# aaasaver_v11.net
KiCad netlist of a schematic drawn in EAGLE
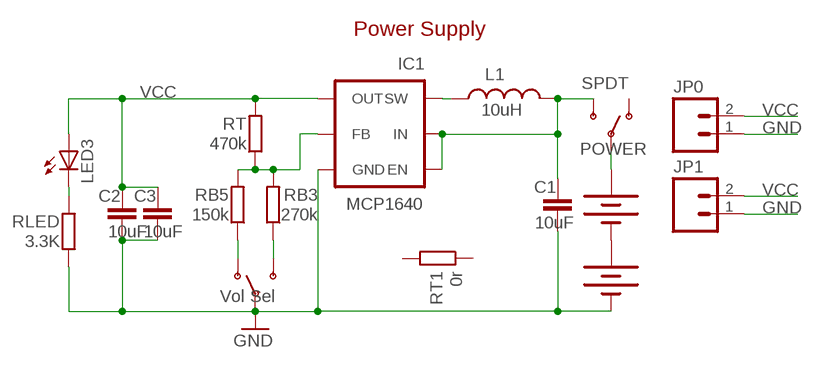
[diagram p0: schematic, sheet 1]

(export (version "E")
  (design (tool "Eeschema 10.0.6"))
  (components
    (comp (ref "AA1")
      (value "BATTERYAAA")
      (footprint "eagle-import:BATTERY-AAA")
      (libsource (lib "eagle-import") (part "BATTERYAAA"))
    )
    (comp (ref "AA2")
      (value "BATTERYAAA")
      (footprint "eagle-import:BATTERY-AAA")
      (libsource (lib "eagle-import") (part "BATTERYAAA"))
    )
    (comp (ref "C1")
      (value "10uF")
      (footprint "eagle-import:C0805")
      (libsource (lib "eagle-import") (part "C-EUC0805"))
    )
    (comp (ref "C2")
      (value "10uF")
      (footprint "eagle-import:C0805")
      (libsource (lib "eagle-import") (part "C-EUC0805"))
    )
    (comp (ref "C3")
      (value "10uF")
      (footprint "eagle-import:C0805")
      (libsource (lib "eagle-import") (part "C-EUC0805"))
    )
    (comp (ref "IC1")
      (value "MCP1640")
      (footprint "eagle-import:TSOT23-6")
      (libsource (lib "eagle-import") (part "MCP1640"))
    )
    (comp (ref "JP0")
      (value "M021X02_NO_SILK")
      (footprint "eagle-import:1X02_NO_SILK")
      (libsource (lib "eagle-import") (part "M021X02_NO_SILK"))
    )
    (comp (ref "JP1")
      (value "M021X02_NO_SILK")
      (footprint "eagle-import:1X02_NO_SILK")
      (libsource (lib "eagle-import") (part "M021X02_NO_SILK"))
    )
    (comp (ref "L1")
      (value "10uH")
      (footprint "eagle-import:INDUCTOR_D45")
      (libsource (lib "eagle-import") (part "INDUCTOR_SMDD45"))
    )
    (comp (ref "LED3")
      (value "0805")
      (footprint "eagle-import:CHIPLED_1206")
      (libsource (lib "eagle-import") (part "LEDCHIPLED_1206"))
    )
    (comp (ref "POWER")
      (value "SPDT")
      (footprint "eagle-import:SWITCH-SPDT-SMD")
      (libsource (lib "eagle-import") (part "SWITCH-SPSTSMD2"))
    )
    (comp (ref "RB3")
      (value "270k")
      (footprint "eagle-import:R0805")
      (libsource (lib "eagle-import") (part "R-EU_R0805"))
    )
    (comp (ref "RB5")
      (value "150k")
      (footprint "eagle-import:R0805")
      (libsource (lib "eagle-import") (part "R-EU_R0805"))
    )
    (comp (ref "RLED")
      (value "3.3K")
      (footprint "eagle-import:R0805")
      (libsource (lib "eagle-import") (part "R-EU_R0805"))
    )
    (comp (ref "RT")
      (value "470k")
      (footprint "eagle-import:R0805")
      (libsource (lib "eagle-import") (part "R-EU_R0805"))
    )
    (comp (ref "RT1")
      (value "0r")
      (footprint "eagle-import:R1206")
      (libsource (lib "eagle-import") (part "R-EU_R1206"))
    )
    (comp (ref "VOL1")
      (value "Vol Sel")
      (footprint "eagle-import:SWITCH-SPDT-SMD")
      (libsource (lib "eagle-import") (part "SWITCH-SPSTSMD2"))
    )
  )
  (nets
    (net (code "1") (name "/VCC") (class "Default")
      (node (ref "C2") (pin "1") (pinfunction "1_1") (pintype "passive"))
      (node (ref "C3") (pin "1") (pinfunction "1_1") (pintype "passive"))
      (node (ref "IC1") (pin "5") (pinfunction "OUT_5") (pintype "passive"))
      (node (ref "JP0") (pin "2") (pinfunction "2_2") (pintype "passive"))
      (node (ref "JP1") (pin "2") (pinfunction "2_2") (pintype "passive"))
      (node (ref "LED3") (pin "A") (pinfunction "A_A") (pintype "passive"))
      (node (ref "RT") (pin "2") (pinfunction "2_2") (pintype "passive"))
    )
    (net (code "2") (name "GND") (class "Default")
      (node (ref "AA2") (pin "GND@1") (pinfunction "-_GND@1") (pintype "power_in"))
      (node (ref "C1") (pin "2") (pinfunction "2_2") (pintype "passive"))
      (node (ref "C2") (pin "2") (pinfunction "2_2") (pintype "passive"))
      (node (ref "C3") (pin "2") (pinfunction "2_2") (pintype "passive"))
      (node (ref "IC1") (pin "2") (pinfunction "GND_2") (pintype "input"))
      (node (ref "JP0") (pin "1") (pinfunction "1_1") (pintype "passive"))
      (node (ref "JP1") (pin "1") (pinfunction "1_1") (pintype "passive"))
      (node (ref "RLED") (pin "1") (pinfunction "1_1") (pintype "passive"))
      (node (ref "VOL1") (pin "2") (pinfunction "P_2") (pintype "passive"))
    )
    (net (code "3") (name "Net-(AA1-+)") (class "Default")
      (node (ref "AA1") (pin "PWR@1") (pinfunction "+_PWR@1") (pintype "power_in"))
      (node (ref "POWER") (pin "2") (pinfunction "P_2") (pintype "passive"))
    )
    (net (code "4") (name "Net-(AA1--)") (class "Default")
      (node (ref "AA1") (pin "GND@1") (pinfunction "-_GND@1") (pintype "power_in"))
      (node (ref "AA2") (pin "PWR@1") (pinfunction "+_PWR@1") (pintype "power_in"))
    )
    (net (code "5") (name "Net-(IC1-EN)") (class "Default")
      (node (ref "C1") (pin "1") (pinfunction "1_1") (pintype "passive"))
      (node (ref "IC1") (pin "3") (pinfunction "EN_3") (pintype "input"))
      (node (ref "IC1") (pin "6") (pinfunction "IN_6") (pintype "input"))
      (node (ref "L1") (pin "P$1") (pinfunction "1_P$1") (pintype "passive"))
      (node (ref "POWER") (pin "3") (pinfunction "S_3") (pintype "passive"))
    )
    (net (code "6") (name "Net-(IC1-FB)") (class "Default")
      (node (ref "IC1") (pin "4") (pinfunction "FB_4") (pintype "input"))
      (node (ref "RB3") (pin "2") (pinfunction "2_2") (pintype "passive"))
      (node (ref "RB5") (pin "2") (pinfunction "2_2") (pintype "passive"))
      (node (ref "RT") (pin "1") (pinfunction "1_1") (pintype "passive"))
    )
    (net (code "7") (name "Net-(IC1-SW)") (class "Default")
      (node (ref "IC1") (pin "1") (pinfunction "SW_1") (pintype "output"))
      (node (ref "L1") (pin "P$2") (pinfunction "2_P$2") (pintype "passive"))
    )
    (net (code "8") (name "Net-(LED3-PadC)") (class "Default")
      (node (ref "LED3") (pin "C") (pinfunction "C_C") (pintype "passive"))
      (node (ref "RLED") (pin "2") (pinfunction "2_2") (pintype "passive"))
    )
    (net (code "9") (name "Net-(VOL1-O)") (class "Default")
      (node (ref "RB5") (pin "1") (pinfunction "1_1") (pintype "passive"))
      (node (ref "VOL1") (pin "1") (pinfunction "O_1") (pintype "passive"))
    )
    (net (code "10") (name "Net-(VOL1-S)") (class "Default")
      (node (ref "RB3") (pin "1") (pinfunction "1_1") (pintype "passive"))
      (node (ref "VOL1") (pin "3") (pinfunction "S_3") (pintype "passive"))
    )
    (net (code "11") (name "unconnected-(POWER-O-Pad1)") (class "Default")
      (node (ref "POWER") (pin "1") (pinfunction "O_1") (pintype "passive"))
    )
    (net (code "12") (name "unconnected-(RT1-Pad1)") (class "Default")
      (node (ref "RT1") (pin "1") (pinfunction "1_1") (pintype "passive"))
    )
    (net (code "13") (name "unconnected-(RT1-Pad2)") (class "Default")
      (node (ref "RT1") (pin "2") (pinfunction "2_2") (pintype "passive"))
    )
  )
)
